# attiny85.net
KiCad netlist of a schematic drawn in EAGLE
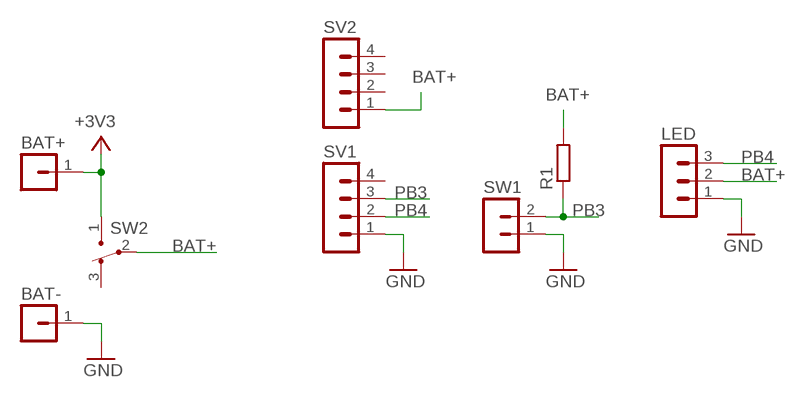
[diagram p0: schematic, sheet 1]

(export (version "E")
  (design (tool "Eeschema 10.0.6"))
  (components
    (comp (ref "BAT+")
      (value "PINHEAD-MA01-1")
      (footprint "eagle-import:PINHEAD-MA01-1")
      (libsource (lib "eagle-import") (part "PINHEAD-MA01-1"))
    )
    (comp (ref "BAT-")
      (value "PINHEAD-MA01-1")
      (footprint "eagle-import:PINHEAD-MA01-1")
      (libsource (lib "eagle-import") (part "PINHEAD-MA01-1"))
    )
    (comp (ref "LED")
      (value "PINHEAD-MA03-1")
      (footprint "eagle-import:PINHEAD-MA03-1")
      (libsource (lib "eagle-import") (part "PINHEAD-MA03-1"))
    )
    (comp (ref "R1")
      (value "R-EU_0204/5")
      (footprint "eagle-import:0204_5")
      (libsource (lib "eagle-import") (part "R-EU_0204/5"))
    )
    (comp (ref "SV1")
      (value "PINHEAD-MA04-1")
      (footprint "eagle-import:PINHEAD-MA04-1")
      (libsource (lib "eagle-import") (part "PINHEAD-MA04-1"))
    )
    (comp (ref "SV2")
      (value "PINHEAD-MA04-1")
      (footprint "eagle-import:PINHEAD-MA04-1")
      (libsource (lib "eagle-import") (part "PINHEAD-MA04-1"))
    )
    (comp (ref "SW1")
      (value "PINHEAD-MA02-1")
      (footprint "eagle-import:PINHEAD-MA02-1")
      (libsource (lib "eagle-import") (part "PINHEAD-MA02-1"))
    )
    (comp (ref "SW2")
      (value "SW3-1")
      (footprint "eagle-import:SW3-1")
      (fields (field (name "MF") "HiLetgo"))
      (libsource (lib "eagle-import") (part "SW3-1"))
    )
  )
  (nets
    (net (code "1") (name "+3V3") (class "Default")
      (node (ref "BAT+") (pin "1") (pinfunction "1_1") (pintype "passive"))
      (node (ref "SW2") (pin "1") (pinfunction "1_1") (pintype "passive"))
    )
    (net (code "2") (name "/BAT+") (class "Default")
      (node (ref "LED") (pin "2") (pinfunction "2_2") (pintype "passive"))
      (node (ref "R1") (pin "2") (pinfunction "2_2") (pintype "passive"))
      (node (ref "SV2") (pin "1") (pinfunction "1_1") (pintype "passive"))
      (node (ref "SW2") (pin "2") (pinfunction "2_2") (pintype "passive"))
    )
    (net (code "3") (name "/PB3") (class "Default")
      (node (ref "R1") (pin "1") (pinfunction "1_1") (pintype "passive"))
      (node (ref "SV1") (pin "3") (pinfunction "3_3") (pintype "passive"))
      (node (ref "SW1") (pin "2") (pinfunction "2_2") (pintype "passive"))
    )
    (net (code "4") (name "/PB4") (class "Default")
      (node (ref "LED") (pin "3") (pinfunction "3_3") (pintype "passive"))
      (node (ref "SV1") (pin "2") (pinfunction "2_2") (pintype "passive"))
    )
    (net (code "5") (name "GND") (class "Default")
      (node (ref "BAT-") (pin "1") (pinfunction "1_1") (pintype "passive"))
      (node (ref "LED") (pin "1") (pinfunction "1_1") (pintype "passive"))
      (node (ref "SV1") (pin "1") (pinfunction "1_1") (pintype "passive"))
      (node (ref "SW1") (pin "1") (pinfunction "1_1") (pintype "passive"))
    )
    (net (code "6") (name "unconnected-(SV1-Pad4)") (class "Default")
      (node (ref "SV1") (pin "4") (pinfunction "4_4") (pintype "passive"))
    )
    (net (code "7") (name "unconnected-(SV2-Pad2)") (class "Default")
      (node (ref "SV2") (pin "2") (pinfunction "2_2") (pintype "passive"))
    )
    (net (code "8") (name "unconnected-(SV2-Pad3)") (class "Default")
      (node (ref "SV2") (pin "3") (pinfunction "3_3") (pintype "passive"))
    )
    (net (code "9") (name "unconnected-(SV2-Pad4)") (class "Default")
      (node (ref "SV2") (pin "4") (pinfunction "4_4") (pintype "passive"))
    )
    (net (code "10") (name "unconnected-(SW2-Pad3)") (class "Default")
      (node (ref "SW2") (pin "3") (pinfunction "3_3") (pintype "passive"))
    )
  )
)
